# Sheet.net
KiCad netlist of a schematic drawn in Altium Designer
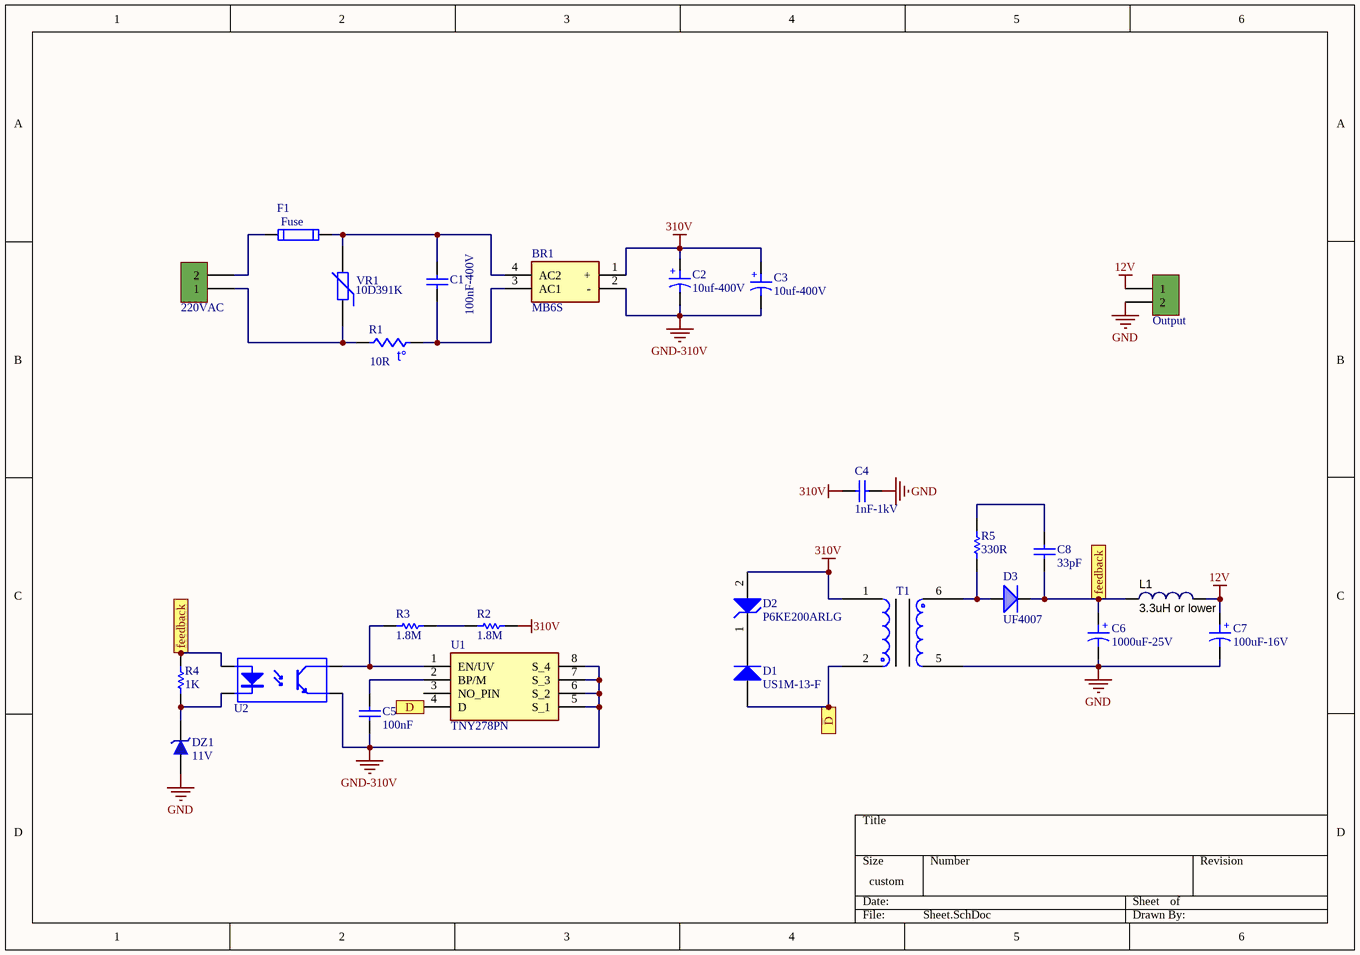
[diagram p0: Sheet.SchDoc]

(export (version "E")
  (design (tool "Eeschema 10.0.6"))
  (components
    (comp (ref "220VAC")
      (value "Phoenix 2 Pin")
      (footprint "Phoenix_2PIN_RA_P5.08mm")
      (libsource (lib "") (part "Phoenix 2 Pin_1"))
    )
    (comp (ref "BR1")
      (value "MB6S")
      (footprint "SamacSys:SOP250P700X270-4N")
      (description "Bridge Rectifier")
      (libsource (lib "*") (part "MB6S"))
    )
    (comp (ref "C1")
      (value "100nF-400V")
      (footprint "Cap-100nF-400V")
      (description "CAP Ceramic Total")
      (fields (field (name "DESIGNER") "Ali Hafizi"))
      (libsource (lib "Altium") (part "CAP CERAMIC TOTAL SIZE"))
    )
    (comp (ref "C2")
      (value "10uf-400V")
      (footprint "Cap electrolitic radial 10x16-5")
      (description "Cap electrolitic radial")
      (fields (field (name "DESIGNER") "Abbas Basereh"))
      (libsource (lib "Schematic") (part "Cap ELECTROLITIC TOTAL SIZE"))
    )
    (comp (ref "C3")
      (value "10uf-400V")
      (footprint "Cap electrolitic radial 10x16-5")
      (description "Cap electrolitic radial")
      (fields (field (name "DESIGNER") "Abbas Basereh"))
      (libsource (lib "Schematic") (part "Cap ELECTROLITIC TOTAL SIZE"))
    )
    (comp (ref "C4")
      (value "1nF-1kV")
      (footprint "CAP1206")
      (description "TOTAL CAPACITOR SMD PACK")
      (fields (field (name "DESIGNER") "Abbas Basereh"))
      (libsource (lib "Altium") (part "CAP SMD PACKAGE"))
    )
    (comp (ref "C5")
      (value "100nF")
      (footprint "CAP805")
      (description "TOTAL CAPACITOR SMD PACK")
      (fields (field (name "DESIGNER") "Abbas Basereh"))
      (libsource (lib "Altium") (part "CAP SMD PACKAGE"))
    )
    (comp (ref "C6")
      (value "1000uF-25V")
      (footprint "Cap electrolitic radial 10x16-5")
      (description "Cap electrolitic radial")
      (fields (field (name "DESIGNER") "Abbas Basereh"))
      (libsource (lib "Altium") (part "Cap ELECTROLITIC TOTAL SIZE"))
    )
    (comp (ref "C7")
      (value "100uF-16V")
      (footprint "Cap electrolitic radial 5x11-2")
      (description "Cap electrolitic radial")
      (fields (field (name "DESIGNER") "Abbas Basereh"))
      (libsource (lib "Altium") (part "Cap ELECTROLITIC TOTAL SIZE"))
    )
    (comp (ref "C8")
      (value "33pF")
      (footprint "CAP805")
      (description "TOTAL CAPACITOR SMD PACK")
      (fields (field (name "DESIGNER") "Abbas Basereh"))
      (libsource (lib "Altium") (part "CAP SMD PACKAGE"))
    )
    (comp (ref "D1")
      (value "US1M-13-F")
      (footprint "DIOD-SMA-2_A_V")
      (description "Ultra-Fast Rectifier, 1 A, 1.7 V, -65 to 150 degC, 2-Pin SMA, RoHS, Tape and Reel")
      (fields (field (name "MANUFACTURER") "Diodes Inc"))
      (libsource (lib "Altium Content Vault") (part "D-AK-2"))
    )
    (comp (ref "D2")
      (value "P6KE200ARLG")
      (footprint "ONSC-SURMETIC40-2-017AA-01")
      (description "600 W Peak Power Transient Voltage Suppressor, 2-Pin Surmetic(TM) 40, Pb-Free, Tape and Reel")
      (fields (field (name "MANUFACTURER") "On Semiconductor"))
      (libsource (lib "Altium Content Vault") (part "ONSC-K1A2-2"))
    )
    (comp (ref "D3")
      (value "UF4007")
      (footprint "DO-41")
      (description "Fast Switching Diodes")
      (fields
        (field (name "MANUFACTURER") "MIC GROUP RECTIFIERS")
        (field (name "MANUFACTURE PART #") "UF4007")
      )
      (libsource (lib "Diode") (part "UF4007"))
    )
    (comp (ref "DZ1")
      (value "11V")
      (footprint "SOD80, LL-34")
      (description "DIODE ZENER GENERAL")
      (fields (field (name "PUBLISHER") "Abbas Basereh"))
      (libsource (lib "Altium") (part "ZENER GENERAL DIODE"))
    )
    (comp (ref "F1")
      (value "FUSE_HOLDER_METAL")
      (footprint "FUSE_5X20MM_4PIN")
      (libsource (lib "Fuse") (part "FUSE METAL 4PIN"))
    )
    (comp (ref "L1")
      (value "3.3uH or lower")
      (footprint "Inductor SMD 3x3.2mm")
      (description "Inductor 4.7µH SMD 3x3.2mm")
      (fields (field (name "TOLERANCE") "±20%"))
      (libsource (lib "Altium") (part "Inductor 4.7µH SMD 3x3.2mm"))
    )
    (comp (ref "Output")
      (value "Phoenix 2 Pin")
      (footprint "Phoenix_2PIN_RA_P5.08mm")
      (libsource (lib "Connector") (part "Phoenix 2 Pin"))
    )
    (comp (ref "R1")
      (value "10R")
      (footprint "NTC_9")
      (description "Thick film, SMD chip Resistor")
      (fields (field (name "MANUFACTURE PART #") "NTC10D-9") (field (name "TOLERANCE") "[20%]"))
      (libsource (lib "Resistor") (part "NTC10D-9"))
    )
    (comp (ref "R2")
      (value "1.8M")
      (footprint "RES0805_(2012X06L)")
      (description "TOTAL SMD RESISTOR PACK")
      (fields (field (name "DESIGNER") "Abbas Basereh"))
      (libsource (lib "Altium") (part "RES SMD PACKAGE"))
    )
    (comp (ref "R3")
      (value "1.8M")
      (footprint "RES0805_(2012X06L)")
      (description "TOTAL SMD RESISTOR PACK")
      (fields (field (name "DESIGNER") "Abbas Basereh"))
      (libsource (lib "Altium") (part "RES SMD PACKAGE"))
    )
    (comp (ref "R4")
      (value "1K")
      (footprint "RES0805_(2012X06L)")
      (description "TOTAL SMD RESISTOR PACK")
      (fields (field (name "DESIGNER") "Abbas Basereh"))
      (libsource (lib "Altium") (part "RES SMD PACKAGE"))
    )
    (comp (ref "R5")
      (value "330R")
      (footprint "RES0805_(2012X06L)")
      (description "TOTAL SMD RESISTOR PACK")
      (fields (field (name "DESIGNER") "Abbas Basereh"))
      (libsource (lib "Altium") (part "RES SMD PACKAGE"))
    )
    (comp (ref "T1")
      (value "EE19-12V")
      (footprint "PCBComponent_1")
      (libsource (lib "EE19-12V") (part "EE19-12V"))
    )
    (comp (ref "U1")
      (value "TNY278PN")
      (footprint "SamacSys:DIP762W56P254L958H406Q8N")
      (description "Integrated Circuit")
      (fields
        (field (name "MANUFACTURER_PART_NUMBER") "TNY274PN")
        (field (name "MOUSER PART NUMBER") "869-TNY274PN")
      )
      (libsource (lib "*") (part "TNY274PN"))
    )
    (comp (ref "U2")
      (value "PC817")
      (footprint "SOP4")
      (description "General Purpose Photocoupler")
      (libsource (lib "Peripheral") (part "PC817"))
    )
    (comp (ref "VR1")
      (value "10D391K")
      (footprint "10D XXX")
      (description "VARISTORS")
      (fields
        (field (name "MANUFACTURER") "china-canada-philipina")
        (field (name "DESIGNER") "Abbas Basereh")
        (field (name "PUBLISHER") "ABBAS BASEREH")
      )
      (libsource (lib "Schematic") (part "VARISTOR (VDR)"))
    )
  )
  (nets
    (net (code "1") (name "/D") (class "Default")
      (node (ref "D1") (pin "1") (pinfunction "A_1") (pintype "passive"))
      (node (ref "T1") (pin "2") (pinfunction "2_2") (pintype "passive"))
      (node (ref "U1") (pin "4") (pinfunction "D_4") (pintype "passive"))
    )
    (net (code "2") (name "/feedback") (class "Default")
      (node (ref "C6") (pin "1") (pinfunction "1_1") (pintype "passive"))
      (node (ref "C8") (pin "1") (pinfunction "1_1") (pintype "passive"))
      (node (ref "D3") (pin "2") (pinfunction "CATHODE_2") (pintype "passive"))
      (node (ref "L1") (pin "1") (pinfunction "1_1") (pintype "passive"))
      (node (ref "R4") (pin "2") (pinfunction "2_2") (pintype "passive"))
      (node (ref "U2") (pin "1") (pinfunction "A_1") (pintype "passive"))
    )
    (net (code "3") (name "12V") (class "Default")
      (node (ref "C7") (pin "1") (pinfunction "1_1") (pintype "passive"))
      (node (ref "L1") (pin "2") (pinfunction "2_2") (pintype "passive"))
      (node (ref "Output") (pin "1") (pinfunction "1_1") (pintype "passive"))
    )
    (net (code "4") (name "310V") (class "Default")
      (node (ref "BR1") (pin "1") (pinfunction "+_1") (pintype "passive"))
      (node (ref "C2") (pin "1") (pinfunction "1_1") (pintype "passive"))
      (node (ref "C3") (pin "1") (pinfunction "1_1") (pintype "passive"))
      (node (ref "C4") (pin "2") (pinfunction "2_2") (pintype "passive"))
      (node (ref "D2") (pin "2") (pinfunction "A_2") (pintype "passive"))
      (node (ref "R2") (pin "2") (pinfunction "2_2") (pintype "passive"))
      (node (ref "T1") (pin "1") (pinfunction "1_1") (pintype "passive"))
    )
    (net (code "5") (name "GND") (class "Default")
      (node (ref "C4") (pin "1") (pinfunction "1_1") (pintype "passive"))
      (node (ref "C6") (pin "2") (pinfunction "2_2") (pintype "passive"))
      (node (ref "C7") (pin "2") (pinfunction "2_2") (pintype "passive"))
      (node (ref "DZ1") (pin "1") (pintype "passive"))
      (node (ref "Output") (pin "2") (pinfunction "2_2") (pintype "passive"))
      (node (ref "T1") (pin "5") (pinfunction "5_5") (pintype "passive"))
    )
    (net (code "6") (name "GND-310V") (class "Default")
      (node (ref "BR1") (pin "2") (pinfunction "-_2") (pintype "passive"))
      (node (ref "C2") (pin "2") (pinfunction "2_2") (pintype "passive"))
      (node (ref "C3") (pin "2") (pinfunction "2_2") (pintype "passive"))
      (node (ref "C5") (pin "1") (pinfunction "1_1") (pintype "passive"))
      (node (ref "U1") (pin "5") (pinfunction "S_1_5") (pintype "passive"))
      (node (ref "U1") (pin "6") (pinfunction "S_2_6") (pintype "passive"))
      (node (ref "U1") (pin "7") (pinfunction "S_3_7") (pintype "passive"))
      (node (ref "U1") (pin "8") (pinfunction "S_4_8") (pintype "passive"))
      (node (ref "U2") (pin "3") (pinfunction "E_3") (pintype "passive"))
    )
    (net (code "7") (name "Net-(220VAC-Pad1)") (class "Default")
      (node (ref "220VAC") (pin "1") (pinfunction "1_1") (pintype "passive"))
      (node (ref "R1") (pin "1") (pinfunction "1_1") (pintype "passive"))
      (node (ref "VR1") (pin "1") (pinfunction "1_1") (pintype "passive"))
    )
    (net (code "8") (name "Net-(220VAC-Pad2)") (class "Default")
      (node (ref "220VAC") (pin "2") (pinfunction "2_2") (pintype "passive"))
      (node (ref "F1") (pin "1") (pinfunction "1_1") (pintype "passive"))
    )
    (net (code "9") (name "Net-(BR1-AC1)") (class "Default")
      (node (ref "BR1") (pin "3") (pinfunction "AC1_3") (pintype "passive"))
      (node (ref "C1") (pin "2") (pinfunction "2_2") (pintype "passive"))
      (node (ref "R1") (pin "2") (pinfunction "2_2") (pintype "passive"))
    )
    (net (code "10") (name "Net-(BR1-AC2)") (class "Default")
      (node (ref "BR1") (pin "4") (pinfunction "AC2_4") (pintype "passive"))
      (node (ref "C1") (pin "1") (pinfunction "1_1") (pintype "passive"))
      (node (ref "F1") (pin "2") (pinfunction "2_2") (pintype "passive"))
      (node (ref "VR1") (pin "2") (pinfunction "2_2") (pintype "passive"))
    )
    (net (code "11") (name "Net-(C8-Pad2)") (class "Default")
      (node (ref "C8") (pin "2") (pinfunction "2_2") (pintype "passive"))
      (node (ref "R5") (pin "2") (pinfunction "2_2") (pintype "passive"))
    )
    (net (code "12") (name "Net-(D1-K)") (class "Default")
      (node (ref "D1") (pin "2") (pinfunction "K_2") (pintype "passive"))
      (node (ref "D2") (pin "1") (pinfunction "K_1") (pintype "passive"))
    )
    (net (code "13") (name "Net-(D3-ANODE)") (class "Default")
      (node (ref "D3") (pin "1") (pinfunction "ANODE_1") (pintype "passive"))
      (node (ref "R5") (pin "1") (pinfunction "1_1") (pintype "passive"))
      (node (ref "T1") (pin "6") (pinfunction "6_6") (pintype "passive"))
    )
    (net (code "14") (name "Net-(R2-Pad1)") (class "Default")
      (node (ref "R2") (pin "1") (pinfunction "1_1") (pintype "passive"))
      (node (ref "R3") (pin "2") (pinfunction "2_2") (pintype "passive"))
    )
    (net (code "15") (name "Net-(U1-BP{slash}M)") (class "Default")
      (node (ref "C5") (pin "2") (pinfunction "2_2") (pintype "passive"))
      (node (ref "U1") (pin "2") (pinfunction "BP/M_2") (pintype "passive"))
    )
    (net (code "16") (name "Net-(U1-EN{slash}UV)") (class "Default")
      (node (ref "R3") (pin "1") (pinfunction "1_1") (pintype "passive"))
      (node (ref "U1") (pin "1") (pinfunction "EN/UV_1") (pintype "passive"))
      (node (ref "U2") (pin "4") (pinfunction "C_4") (pintype "passive"))
    )
    (net (code "17") (name "Net-(U2-K)") (class "Default")
      (node (ref "DZ1") (pin "2") (pintype "passive"))
      (node (ref "R4") (pin "1") (pinfunction "1_1") (pintype "passive"))
      (node (ref "U2") (pin "2") (pinfunction "K_2") (pintype "passive"))
    )
    (net (code "18") (name "unconnected-(U1-NO_PIN-Pad3)") (class "Default")
      (node (ref "U1") (pin "3") (pinfunction "NO_PIN_3") (pintype "passive"))
    )
  )
)
